# NanoRS485-MySens-v024.net
KiCad netlist of a schematic drawn in EAGLE
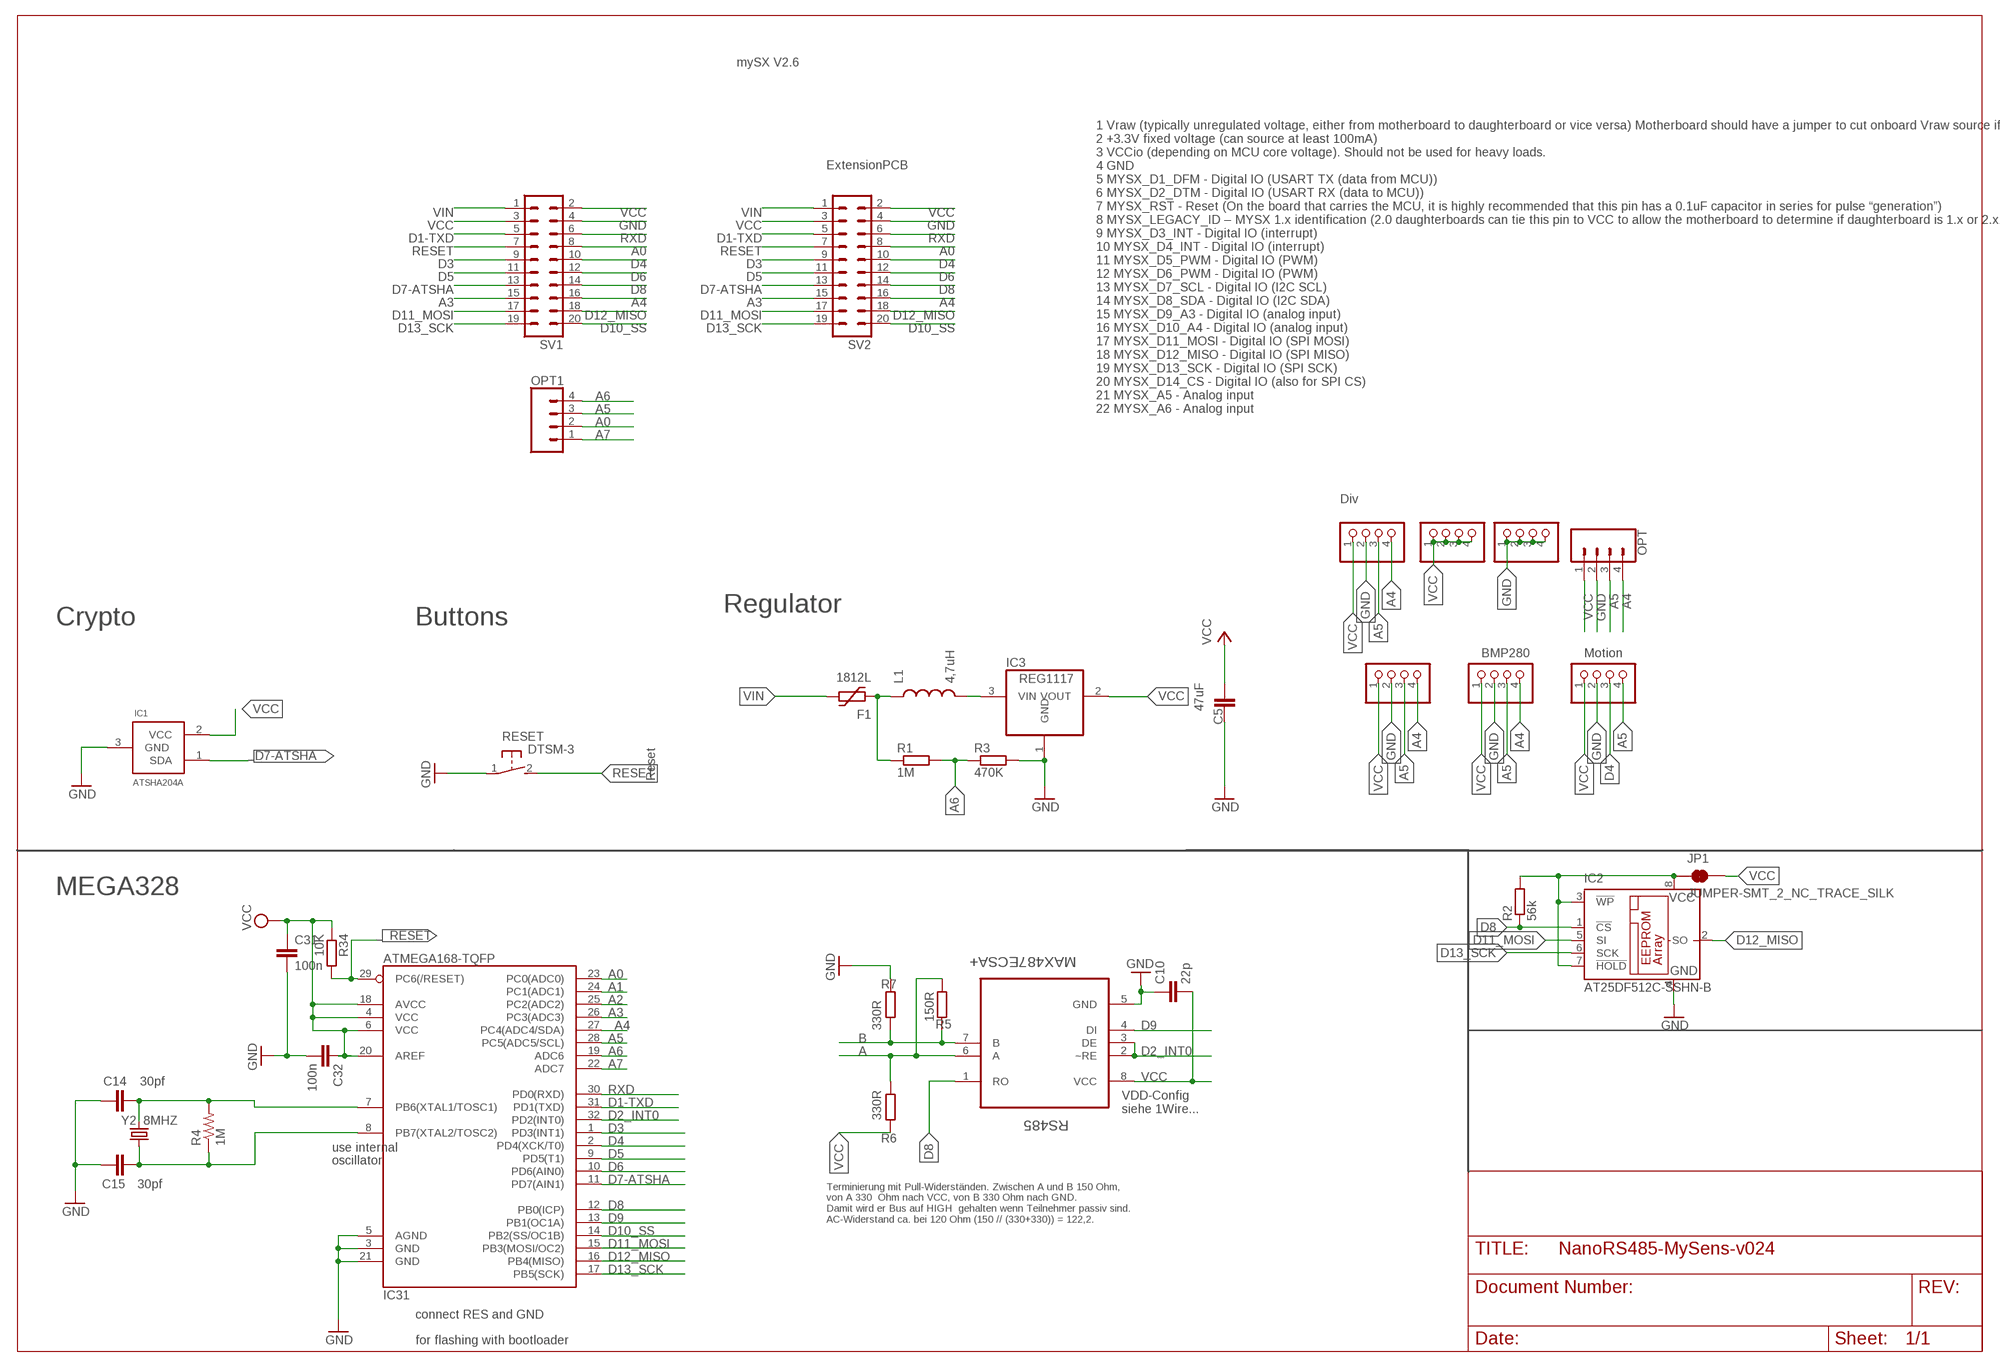
[diagram p0: schematic, sheet 1, part 1 of 2]
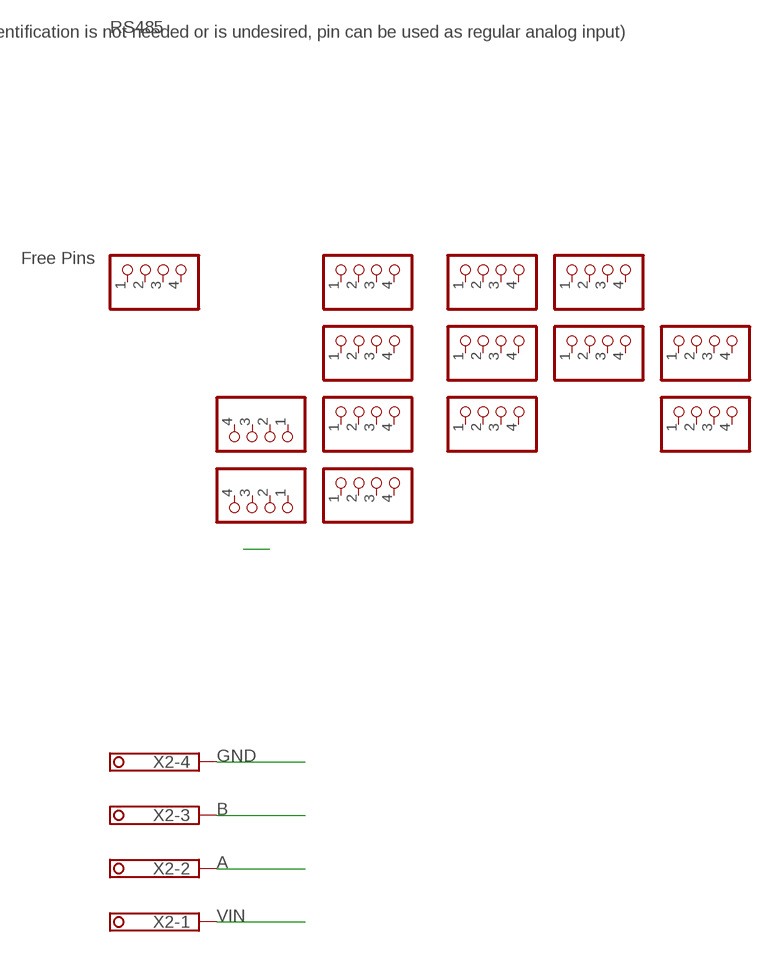
[diagram p1: schematic, sheet 1, part 2 of 2]

(export (version "E")
  (design (tool "Eeschema 10.0.6"))
  (components
    (comp (ref "BH1750")
      (value "PINHD-1X04_2.54-S")
      (footprint "eagle-import:1X04-S")
      (libsource (lib "eagle-import") (part "PINHD-1X04_2.54-S"))
    )
    (comp (ref "C5")
      (value "47uF")
      (footprint "eagle-import:C1210")
      (libsource (lib "eagle-import") (part "C-EUC1210"))
    )
    (comp (ref "C10")
      (value "22p")
      (footprint "eagle-import:C0805")
      (libsource (lib "eagle-import") (part "C-EUC0805"))
    )
    (comp (ref "C14")
      (value "30pf")
      (footprint "eagle-import:0805")
      (libsource (lib "eagle-import") (part "CAP0805"))
    )
    (comp (ref "C15")
      (value "30pf")
      (footprint "eagle-import:0805")
      (libsource (lib "eagle-import") (part "CAP0805"))
    )
    (comp (ref "C31")
      (value "100n")
      (footprint "eagle-import:C0805")
      (libsource (lib "eagle-import") (part "C-EUC0805"))
    )
    (comp (ref "C32")
      (value "100n")
      (footprint "eagle-import:C0805")
      (libsource (lib "eagle-import") (part "C-EUC0805"))
    )
    (comp (ref "F1")
      (value "1812L")
      (footprint "eagle-import:1812L")
      (libsource (lib "eagle-import") (part "1812L"))
    )
    (comp (ref "I2C-1")
      (value "PINHD-1X04_2.54-S")
      (footprint "eagle-import:1X04-S")
      (libsource (lib "eagle-import") (part "PINHD-1X04_2.54-S"))
    )
    (comp (ref "I2C-2")
      (value "PINHD-1X04_2.54-S")
      (footprint "eagle-import:1X04-S")
      (libsource (lib "eagle-import") (part "PINHD-1X04_2.54-S"))
    )
    (comp (ref "IC1")
      (value "ATSHA204A")
      (footprint "eagle-import:SOT23")
      (libsource (lib "eagle-import") (part "ATSHA204A"))
    )
    (comp (ref "IC2")
      (value "AT25DF512C-SSHN-B")
      (footprint "eagle-import:SO-08")
      (fields (field (name "MF") "MICROCHIP") (field (name "MPN") "25AA080/SN"))
      (libsource (lib "eagle-import") (part "25SNAA080"))
    )
    (comp (ref "IC3")
      (value "REG1117")
      (footprint "eagle-import:SOT223")
      (libsource (lib "eagle-import") (part "REG1117"))
    )
    (comp (ref "IC31")
      (value "ATMEGA168-TQFP")
      (footprint "eagle-import:TQFP32-08")
      (libsource (lib "eagle-import") (part "ATMEGA168-TQFP"))
    )
    (comp (ref "JP1")
      (value "JUMPER-SMT_2_NC_TRACE_SILK")
      (footprint "eagle-import:SMT-JUMPER_2_NC_TRACE_SILK")
      (libsource (lib "eagle-import") (part "JUMPER-SMT_2_NC_TRACE_SILK"))
    )
    (comp (ref "JP2")
      (value "PINHD-1X04_2.54-S")
      (footprint "eagle-import:1X04-S")
      (libsource (lib "eagle-import") (part "PINHD-1X04_2.54-S"))
    )
    (comp (ref "JP3")
      (value "PINHD-1X04_2.54-S")
      (footprint "eagle-import:1X04-S")
      (libsource (lib "eagle-import") (part "PINHD-1X04_2.54-S"))
    )
    (comp (ref "JP5")
      (value "PINHD-1X04_2.54-S")
      (footprint "eagle-import:1X04-S")
      (libsource (lib "eagle-import") (part "PINHD-1X04_2.54-S"))
    )
    (comp (ref "JP6")
      (value "PINHD-1X04_2.54-S")
      (footprint "eagle-import:1X04-S")
      (libsource (lib "eagle-import") (part "PINHD-1X04_2.54-S"))
    )
    (comp (ref "JP7")
      (value "PINHD-1X04_2.54-S")
      (footprint "eagle-import:1X04-S")
      (libsource (lib "eagle-import") (part "PINHD-1X04_2.54-S"))
    )
    (comp (ref "JP8")
      (value "PINHD-1X04_2.54-S")
      (footprint "eagle-import:1X04-S")
      (libsource (lib "eagle-import") (part "PINHD-1X04_2.54-S"))
    )
    (comp (ref "JP10")
      (value "PINHD-1X04_2.54-S")
      (footprint "eagle-import:1X04-S")
      (libsource (lib "eagle-import") (part "PINHD-1X04_2.54-S"))
    )
    (comp (ref "JP13")
      (value "PINHD-1X04_2.54-S")
      (footprint "eagle-import:1X04-S")
      (libsource (lib "eagle-import") (part "PINHD-1X04_2.54-S"))
    )
    (comp (ref "JP14")
      (value "PINHD-1X04_2.54-S")
      (footprint "eagle-import:1X04-S")
      (libsource (lib "eagle-import") (part "PINHD-1X04_2.54-S"))
    )
    (comp (ref "JP15")
      (value "PINHD-1X04_2.54-S")
      (footprint "eagle-import:1X04-S")
      (libsource (lib "eagle-import") (part "PINHD-1X04_2.54-S"))
    )
    (comp (ref "JP16")
      (value "PINHD-1X04_2.54-S")
      (footprint "eagle-import:1X04-S")
      (libsource (lib "eagle-import") (part "PINHD-1X04_2.54-S"))
    )
    (comp (ref "JP18")
      (value "PINHD-1X04_2.54-S")
      (footprint "eagle-import:1X04-S")
      (libsource (lib "eagle-import") (part "PINHD-1X04_2.54-S"))
    )
    (comp (ref "JP19")
      (value "PINHD-1X04_2.54-S")
      (footprint "eagle-import:1X04-S")
      (libsource (lib "eagle-import") (part "PINHD-1X04_2.54-S"))
    )
    (comp (ref "JP20")
      (value "PINHD-1X04_2.54-S")
      (footprint "eagle-import:1X04-S")
      (libsource (lib "eagle-import") (part "PINHD-1X04_2.54-S"))
    )
    (comp (ref "JP21")
      (value "PINHD-1X04_2.54-S")
      (footprint "eagle-import:1X04-S")
      (libsource (lib "eagle-import") (part "PINHD-1X04_2.54-S"))
    )
    (comp (ref "JP23")
      (value "PINHD-1X04_2.54-S")
      (footprint "eagle-import:1X04-S")
      (libsource (lib "eagle-import") (part "PINHD-1X04_2.54-S"))
    )
    (comp (ref "L1")
      (value "4,7uH")
      (footprint "eagle-import:0805")
      (libsource (lib "eagle-import") (part "INDUCTOR0805"))
    )
    (comp (ref "MOTION")
      (value "PINHD-1X04_2.54-S")
      (footprint "eagle-import:1X04-S")
      (libsource (lib "eagle-import") (part "PINHD-1X04_2.54-S"))
    )
    (comp (ref "OPT")
      (value "CONN_04")
      (footprint "eagle-import:1X04")
      (libsource (lib "eagle-import") (part "CONN_04"))
    )
    (comp (ref "OPT1")
      (value "CONN_04")
      (footprint "eagle-import:1X04")
      (libsource (lib "eagle-import") (part "CONN_04"))
    )
    (comp (ref "R1")
      (value "1M")
      (footprint "eagle-import:R0805")
      (libsource (lib "eagle-import") (part "R-EU_R0805"))
    )
    (comp (ref "R2")
      (value "56k")
      (footprint "eagle-import:M0805")
      (libsource (lib "eagle-import") (part "resistor_R-EU_M0805"))
    )
    (comp (ref "R3")
      (value "470K")
      (footprint "eagle-import:R0805")
      (libsource (lib "eagle-import") (part "R-EU_R0805"))
    )
    (comp (ref "R4")
      (value "1M")
      (footprint "eagle-import:0805")
      (libsource (lib "eagle-import") (part "RESISTOR0805-RES"))
    )
    (comp (ref "R5")
      (value "150R")
      (footprint "eagle-import:R0805")
      (libsource (lib "eagle-import") (part "R-EU_R0805"))
    )
    (comp (ref "R6")
      (value "330R")
      (footprint "eagle-import:R0805")
      (libsource (lib "eagle-import") (part "R-EU_R0805"))
    )
    (comp (ref "R7")
      (value "330R")
      (footprint "eagle-import:R0805")
      (libsource (lib "eagle-import") (part "R-EU_R0805"))
    )
    (comp (ref "R34")
      (value "10K")
      (footprint "eagle-import:R0805")
      (libsource (lib "eagle-import") (part "R-EU_R0805"))
    )
    (comp (ref "RESET")
      (value "DTSM-3")
      (footprint "eagle-import:DTSM-3")
      (libsource (lib "eagle-import") (part "DTSM-3"))
    )
    (comp (ref "RS485")
      (value "MAX487ECSA+")
      (footprint "eagle-import:SOIC127P600X175-8N")
      (libsource (lib "eagle-import") (part "MAX487ECSA+"))
    )
    (comp (ref "SV1")
      (value "MA10-2")
      (footprint "eagle-import:MA10-2")
      (libsource (lib "eagle-import") (part "MA10-2"))
    )
    (comp (ref "SV2")
      (value "MA10-2")
      (footprint "eagle-import:MA10-2")
      (libsource (lib "eagle-import") (part "MA10-2"))
    )
    (comp (ref "X2")
      (value "1751264")
      (footprint "eagle-import:1751264")
      (libsource (lib "eagle-import") (part "1751264"))
    )
    (comp (ref "Y2")
      (value "8MHZ")
      (footprint "eagle-import:CRYSTAL-TXC-7A")
      (libsource (lib "eagle-import") (part "CRYSTALTXC-7A"))
    )
  )
  (nets
    (net (code "1") (name "/A") (class "Default")
      (node (ref "R5") (pin "1") (pinfunction "1_1") (pintype "passive"))
      (node (ref "R6") (pin "2") (pinfunction "2_2") (pintype "passive"))
      (node (ref "RS485") (pin "6") (pinfunction "A_6") (pintype "bidirectional"))
      (node (ref "X2") (pin "2") (pinfunction "K_2") (pintype "passive"))
    )
    (net (code "2") (name "/A0") (class "Default")
      (node (ref "IC31") (pin "23") (pinfunction "PC0(ADC0)_23") (pintype "bidirectional"))
      (node (ref "OPT1") (pin "2") (pinfunction "2_2") (pintype "passive"))
      (node (ref "SV1") (pin "8") (pinfunction "8_8") (pintype "passive"))
      (node (ref "SV2") (pin "8") (pinfunction "8_8") (pintype "passive"))
    )
    (net (code "3") (name "/A1") (class "Default")
      (node (ref "IC31") (pin "24") (pinfunction "PC1(ADC1)_24") (pintype "bidirectional"))
    )
    (net (code "4") (name "/A2") (class "Default")
      (node (ref "IC31") (pin "25") (pinfunction "PC2(ADC2)_25") (pintype "bidirectional"))
    )
    (net (code "5") (name "/A3") (class "Default")
      (node (ref "IC31") (pin "26") (pinfunction "PC3(ADC3)_26") (pintype "bidirectional"))
      (node (ref "SV1") (pin "15") (pinfunction "15_15") (pintype "passive"))
      (node (ref "SV2") (pin "15") (pinfunction "15_15") (pintype "passive"))
    )
    (net (code "6") (name "/A7") (class "Default")
      (node (ref "IC31") (pin "22") (pinfunction "ADC7_22") (pintype "bidirectional"))
      (node (ref "OPT1") (pin "1") (pinfunction "1_1") (pintype "passive"))
    )
    (net (code "7") (name "/B") (class "Default")
      (node (ref "R5") (pin "2") (pinfunction "2_2") (pintype "passive"))
      (node (ref "R7") (pin "1") (pinfunction "1_1") (pintype "passive"))
      (node (ref "RS485") (pin "7") (pinfunction "B_7") (pintype "bidirectional"))
      (node (ref "X2") (pin "3") (pinfunction "K_3") (pintype "passive"))
    )
    (net (code "8") (name "/D1-TXD") (class "Default")
      (node (ref "IC31") (pin "31") (pinfunction "PD1(TXD)_31") (pintype "bidirectional"))
      (node (ref "SV1") (pin "5") (pinfunction "5_5") (pintype "passive"))
      (node (ref "SV2") (pin "5") (pinfunction "5_5") (pintype "passive"))
    )
    (net (code "9") (name "/D2_INT0") (class "Default")
      (node (ref "IC31") (pin "32") (pinfunction "PD2(INT0)_32") (pintype "bidirectional"))
      (node (ref "RS485") (pin "2") (pinfunction "~{RE}_2") (pintype "input"))
      (node (ref "RS485") (pin "3") (pinfunction "DE_3") (pintype "input"))
    )
    (net (code "10") (name "/D3") (class "Default")
      (node (ref "IC31") (pin "1") (pinfunction "PD3(INT1)_1") (pintype "bidirectional"))
      (node (ref "SV1") (pin "9") (pinfunction "9_9") (pintype "passive"))
      (node (ref "SV2") (pin "9") (pinfunction "9_9") (pintype "passive"))
    )
    (net (code "11") (name "/D5") (class "Default")
      (node (ref "IC31") (pin "9") (pinfunction "PD5(T1)_9") (pintype "bidirectional"))
      (node (ref "SV1") (pin "11") (pinfunction "11_11") (pintype "passive"))
      (node (ref "SV2") (pin "11") (pinfunction "11_11") (pintype "passive"))
    )
    (net (code "12") (name "/D6") (class "Default")
      (node (ref "IC31") (pin "10") (pinfunction "PD6(AIN0)_10") (pintype "bidirectional"))
      (node (ref "SV1") (pin "12") (pinfunction "12_12") (pintype "passive"))
      (node (ref "SV2") (pin "12") (pinfunction "12_12") (pintype "passive"))
    )
    (net (code "13") (name "/D7-ATSHA") (class "Default")
      (node (ref "IC1") (pin "1") (pinfunction "SDA_1") (pintype "bidirectional"))
      (node (ref "IC31") (pin "11") (pinfunction "PD7(AIN1)_11") (pintype "bidirectional"))
      (node (ref "SV1") (pin "13") (pinfunction "13_13") (pintype "passive"))
      (node (ref "SV2") (pin "13") (pinfunction "13_13") (pintype "passive"))
    )
    (net (code "14") (name "/D9") (class "Default")
      (node (ref "IC31") (pin "13") (pinfunction "PB1(OC1A)_13") (pintype "bidirectional"))
      (node (ref "RS485") (pin "4") (pinfunction "DI_4") (pintype "input"))
    )
    (net (code "15") (name "/D10_SS") (class "Default")
      (node (ref "IC31") (pin "14") (pinfunction "PB2(SS/OC1B)_14") (pintype "bidirectional"))
      (node (ref "SV1") (pin "20") (pinfunction "20_20") (pintype "passive"))
      (node (ref "SV2") (pin "20") (pinfunction "20_20") (pintype "passive"))
    )
    (net (code "16") (name "/RXD") (class "Default")
      (node (ref "IC31") (pin "30") (pinfunction "PD0(RXD)_30") (pintype "bidirectional"))
      (node (ref "SV1") (pin "6") (pinfunction "6_6") (pintype "passive"))
      (node (ref "SV2") (pin "6") (pinfunction "6_6") (pintype "passive"))
    )
    (net (code "17") (name "A4") (class "Default")
      (node (ref "BH1750") (pin "4") (pinfunction "4_4") (pintype "passive"))
      (node (ref "I2C-1") (pin "4") (pinfunction "4_4") (pintype "passive"))
      (node (ref "I2C-2") (pin "4") (pinfunction "4_4") (pintype "passive"))
      (node (ref "IC31") (pin "27") (pinfunction "PC4(ADC4/SDA)_27") (pintype "bidirectional"))
      (node (ref "OPT") (pin "4") (pinfunction "4_4") (pintype "passive"))
      (node (ref "SV1") (pin "16") (pinfunction "16_16") (pintype "passive"))
      (node (ref "SV2") (pin "16") (pinfunction "16_16") (pintype "passive"))
    )
    (net (code "18") (name "A5") (class "Default")
      (node (ref "BH1750") (pin "3") (pinfunction "3_3") (pintype "passive"))
      (node (ref "I2C-1") (pin "3") (pinfunction "3_3") (pintype "passive"))
      (node (ref "I2C-2") (pin "3") (pinfunction "3_3") (pintype "passive"))
      (node (ref "IC31") (pin "28") (pinfunction "PC5(ADC5/SCL)_28") (pintype "bidirectional"))
      (node (ref "MOTION") (pin "4") (pinfunction "4_4") (pintype "passive"))
      (node (ref "OPT") (pin "3") (pinfunction "3_3") (pintype "passive"))
      (node (ref "OPT1") (pin "3") (pinfunction "3_3") (pintype "passive"))
    )
    (net (code "19") (name "A6") (class "Default")
      (node (ref "IC31") (pin "19") (pinfunction "ADC6_19") (pintype "bidirectional"))
      (node (ref "OPT1") (pin "4") (pinfunction "4_4") (pintype "passive"))
      (node (ref "R1") (pin "2") (pinfunction "2_2") (pintype "passive"))
      (node (ref "R3") (pin "1") (pinfunction "1_1") (pintype "passive"))
    )
    (net (code "20") (name "D4") (class "Default")
      (node (ref "IC31") (pin "2") (pinfunction "PD4(XCK/T0)_2") (pintype "bidirectional"))
      (node (ref "MOTION") (pin "3") (pinfunction "3_3") (pintype "passive"))
      (node (ref "SV1") (pin "10") (pinfunction "10_10") (pintype "passive"))
      (node (ref "SV2") (pin "10") (pinfunction "10_10") (pintype "passive"))
    )
    (net (code "21") (name "D8") (class "Default")
      (node (ref "IC2") (pin "1") (pinfunction "~{CS}_1") (pintype "input"))
      (node (ref "IC31") (pin "12") (pinfunction "PB0(ICP)_12") (pintype "bidirectional"))
      (node (ref "R2") (pin "1") (pinfunction "1_1") (pintype "passive"))
      (node (ref "RS485") (pin "1") (pinfunction "RO_1") (pintype "output"))
      (node (ref "SV1") (pin "14") (pinfunction "14_14") (pintype "passive"))
      (node (ref "SV2") (pin "14") (pinfunction "14_14") (pintype "passive"))
    )
    (net (code "22") (name "D11_MOSI") (class "Default")
      (node (ref "IC2") (pin "5") (pinfunction "SI_5") (pintype "input"))
      (node (ref "IC31") (pin "15") (pinfunction "PB3(MOSI/OC2)_15") (pintype "bidirectional"))
      (node (ref "SV1") (pin "17") (pinfunction "17_17") (pintype "passive"))
      (node (ref "SV2") (pin "17") (pinfunction "17_17") (pintype "passive"))
    )
    (net (code "23") (name "D12_MISO") (class "Default")
      (node (ref "IC2") (pin "2") (pinfunction "SO_2") (pintype "bidirectional"))
      (node (ref "IC31") (pin "16") (pinfunction "PB4(MISO)_16") (pintype "bidirectional"))
      (node (ref "SV1") (pin "18") (pinfunction "18_18") (pintype "passive"))
      (node (ref "SV2") (pin "18") (pinfunction "18_18") (pintype "passive"))
    )
    (net (code "24") (name "D13_SCK") (class "Default")
      (node (ref "IC2") (pin "6") (pinfunction "SCK_6") (pintype "input"))
      (node (ref "IC31") (pin "17") (pinfunction "PB5(SCK)_17") (pintype "bidirectional"))
      (node (ref "SV1") (pin "19") (pinfunction "19_19") (pintype "passive"))
      (node (ref "SV2") (pin "19") (pinfunction "19_19") (pintype "passive"))
    )
    (net (code "25") (name "GND") (class "Default")
      (node (ref "BH1750") (pin "2") (pinfunction "2_2") (pintype "passive"))
      (node (ref "C10") (pin "1") (pinfunction "1_1") (pintype "passive"))
      (node (ref "C14") (pin "1") (pinfunction "1_1") (pintype "passive"))
      (node (ref "C15") (pin "1") (pinfunction "1_1") (pintype "passive"))
      (node (ref "C31") (pin "2") (pinfunction "2_2") (pintype "passive"))
      (node (ref "C32") (pin "2") (pinfunction "2_2") (pintype "passive"))
      (node (ref "C5") (pin "1") (pinfunction "1_1") (pintype "passive"))
      (node (ref "I2C-1") (pin "2") (pinfunction "2_2") (pintype "passive"))
      (node (ref "I2C-2") (pin "2") (pinfunction "2_2") (pintype "passive"))
      (node (ref "IC1") (pin "3") (pinfunction "GND_3") (pintype "bidirectional"))
      (node (ref "IC2") (pin "4") (pinfunction "GND_4") (pintype "power_in"))
      (node (ref "IC3") (pin "1") (pinfunction "GND_1") (pintype "power_in"))
      (node (ref "IC31") (pin "21") (pinfunction "GND_21") (pintype "bidirectional"))
      (node (ref "IC31") (pin "3") (pinfunction "GND_3") (pintype "bidirectional"))
      (node (ref "IC31") (pin "5") (pinfunction "AGND_5") (pintype "bidirectional"))
      (node (ref "JP2") (pin "1") (pinfunction "1_1") (pintype "passive"))
      (node (ref "JP2") (pin "2") (pinfunction "2_2") (pintype "passive"))
      (node (ref "JP2") (pin "3") (pinfunction "3_3") (pintype "passive"))
      (node (ref "JP2") (pin "4") (pinfunction "4_4") (pintype "passive"))
      (node (ref "MOTION") (pin "2") (pinfunction "2_2") (pintype "passive"))
      (node (ref "OPT") (pin "2") (pinfunction "2_2") (pintype "passive"))
      (node (ref "R3") (pin "2") (pinfunction "2_2") (pintype "passive"))
      (node (ref "R7") (pin "2") (pinfunction "2_2") (pintype "passive"))
      (node (ref "RESET") (pin "1") (pinfunction "1_1") (pintype "passive"))
      (node (ref "RS485") (pin "5") (pinfunction "GND_5") (pintype "passive"))
      (node (ref "SV1") (pin "4") (pinfunction "4_4") (pintype "passive"))
      (node (ref "SV2") (pin "4") (pinfunction "4_4") (pintype "passive"))
      (node (ref "X2") (pin "4") (pinfunction "K_4") (pintype "passive"))
    )
    (net (code "26") (name "Net-(F1-1)") (class "Default")
      (node (ref "F1") (pin "P$1") (pinfunction "1_P$1") (pintype "passive"))
      (node (ref "L1") (pin "1") (pinfunction "1_1") (pintype "passive"))
      (node (ref "R1") (pin "1") (pinfunction "1_1") (pintype "passive"))
    )
    (net (code "27") (name "Net-(IC2-VCC)") (class "Default")
      (node (ref "IC2") (pin "3") (pinfunction "~{WP}_3") (pintype "input"))
      (node (ref "IC2") (pin "7") (pinfunction "~{HOLD}_7") (pintype "input"))
      (node (ref "IC2") (pin "8") (pinfunction "VCC_8") (pintype "power_in"))
      (node (ref "JP1") (pin "1") (pinfunction "1_1") (pintype "passive"))
      (node (ref "R2") (pin "2") (pinfunction "2_2") (pintype "passive"))
    )
    (net (code "28") (name "Net-(IC3-VIN)") (class "Default")
      (node (ref "IC3") (pin "3") (pinfunction "VIN_3") (pintype "input"))
      (node (ref "L1") (pin "2") (pinfunction "2_2") (pintype "passive"))
    )
    (net (code "29") (name "Net-(IC31-PB6(XTAL1{slash}TOSC1))") (class "Default")
      (node (ref "C14") (pin "2") (pinfunction "2_2") (pintype "passive"))
      (node (ref "IC31") (pin "7") (pinfunction "PB6(XTAL1/TOSC1)_7") (pintype "bidirectional"))
      (node (ref "R4") (pin "2") (pinfunction "2_2") (pintype "passive"))
      (node (ref "Y2") (pin "P$2") (pinfunction "2_P$2") (pintype "passive"))
    )
    (net (code "30") (name "Net-(IC31-PB7(XTAL2{slash}TOSC2))") (class "Default")
      (node (ref "C15") (pin "2") (pinfunction "2_2") (pintype "passive"))
      (node (ref "IC31") (pin "8") (pinfunction "PB7(XTAL2/TOSC2)_8") (pintype "bidirectional"))
      (node (ref "R4") (pin "1") (pinfunction "1_1") (pintype "passive"))
      (node (ref "Y2") (pin "P$1") (pinfunction "1_P$1") (pintype "passive"))
    )
    (net (code "31") (name "RESET") (class "Default")
      (node (ref "IC31") (pin "29") (pinfunction "PC6(/RESET)_29") (pintype "bidirectional"))
      (node (ref "R34") (pin "2") (pinfunction "2_2") (pintype "passive"))
      (node (ref "RESET") (pin "2") (pinfunction "2_2") (pintype "passive"))
      (node (ref "SV1") (pin "7") (pinfunction "7_7") (pintype "passive"))
      (node (ref "SV2") (pin "7") (pinfunction "7_7") (pintype "passive"))
    )
    (net (code "32") (name "VCC") (class "Default")
      (node (ref "BH1750") (pin "1") (pinfunction "1_1") (pintype "passive"))
      (node (ref "C10") (pin "2") (pinfunction "2_2") (pintype "passive"))
      (node (ref "C31") (pin "1") (pinfunction "1_1") (pintype "passive"))
      (node (ref "C32") (pin "1") (pinfunction "1_1") (pintype "passive"))
      (node (ref "C5") (pin "2") (pinfunction "2_2") (pintype "passive"))
      (node (ref "I2C-1") (pin "1") (pinfunction "1_1") (pintype "passive"))
      (node (ref "I2C-2") (pin "1") (pinfunction "1_1") (pintype "passive"))
      (node (ref "IC1") (pin "2") (pinfunction "VCC_2") (pintype "bidirectional"))
      (node (ref "IC3") (pin "2") (pinfunction "VOUT_2") (pintype "output"))
      (node (ref "IC31") (pin "18") (pinfunction "AVCC_18") (pintype "bidirectional"))
      (node (ref "IC31") (pin "20") (pinfunction "AREF_20") (pintype "bidirectional"))
      (node (ref "IC31") (pin "4") (pinfunction "VCC_4") (pintype "bidirectional"))
      (node (ref "IC31") (pin "6") (pinfunction "VCC_6") (pintype "bidirectional"))
      (node (ref "JP1") (pin "2") (pinfunction "2_2") (pintype "passive"))
      (node (ref "JP3") (pin "1") (pinfunction "1_1") (pintype "passive"))
      (node (ref "JP3") (pin "2") (pinfunction "2_2") (pintype "passive"))
      (node (ref "JP3") (pin "3") (pinfunction "3_3") (pintype "passive"))
      (node (ref "JP3") (pin "4") (pinfunction "4_4") (pintype "passive"))
      (node (ref "MOTION") (pin "1") (pinfunction "1_1") (pintype "passive"))
      (node (ref "OPT") (pin "1") (pinfunction "1_1") (pintype "passive"))
      (node (ref "R34") (pin "1") (pinfunction "1_1") (pintype "passive"))
      (node (ref "R6") (pin "1") (pinfunction "1_1") (pintype "passive"))
      (node (ref "RS485") (pin "8") (pinfunction "VCC_8") (pintype "power_in"))
      (node (ref "SV1") (pin "2") (pinfunction "2_2") (pintype "passive"))
      (node (ref "SV1") (pin "3") (pinfunction "3_3") (pintype "passive"))
      (node (ref "SV2") (pin "2") (pinfunction "2_2") (pintype "passive"))
      (node (ref "SV2") (pin "3") (pinfunction "3_3") (pintype "passive"))
    )
    (net (code "33") (name "VIN") (class "Default")
      (node (ref "F1") (pin "P$2") (pinfunction "2_P$2") (pintype "passive"))
      (node (ref "SV1") (pin "1") (pinfunction "1_1") (pintype "passive"))
      (node (ref "SV2") (pin "1") (pinfunction "1_1") (pintype "passive"))
      (node (ref "X2") (pin "1") (pinfunction "K_1") (pintype "passive"))
    )
    (net (code "34") (name "unconnected-(JP5-Pad1)") (class "Default")
      (node (ref "JP5") (pin "1") (pinfunction "1_1") (pintype "passive"))
    )
    (net (code "35") (name "unconnected-(JP5-Pad2)") (class "Default")
      (node (ref "JP5") (pin "2") (pinfunction "2_2") (pintype "passive"))
    )
    (net (code "36") (name "unconnected-(JP5-Pad3)") (class "Default")
      (node (ref "JP5") (pin "3") (pinfunction "3_3") (pintype "passive"))
    )
    (net (code "37") (name "unconnected-(JP5-Pad4)") (class "Default")
      (node (ref "JP5") (pin "4") (pinfunction "4_4") (pintype "passive"))
    )
    (net (code "38") (name "unconnected-(JP6-Pad1)") (class "Default")
      (node (ref "JP6") (pin "1") (pinfunction "1_1") (pintype "passive"))
    )
    (net (code "39") (name "unconnected-(JP6-Pad2)") (class "Default")
      (node (ref "JP6") (pin "2") (pinfunction "2_2") (pintype "passive"))
    )
    (net (code "40") (name "unconnected-(JP6-Pad3)") (class "Default")
      (node (ref "JP6") (pin "3") (pinfunction "3_3") (pintype "passive"))
    )
    (net (code "41") (name "unconnected-(JP6-Pad4)") (class "Default")
      (node (ref "JP6") (pin "4") (pinfunction "4_4") (pintype "passive"))
    )
    (net (code "42") (name "unconnected-(JP7-Pad1)") (class "Default")
      (node (ref "JP7") (pin "1") (pinfunction "1_1") (pintype "passive"))
    )
    (net (code "43") (name "unconnected-(JP7-Pad2)") (class "Default")
      (node (ref "JP7") (pin "2") (pinfunction "2_2") (pintype "passive"))
    )
    (net (code "44") (name "unconnected-(JP7-Pad3)") (class "Default")
      (node (ref "JP7") (pin "3") (pinfunction "3_3") (pintype "passive"))
    )
    (net (code "45") (name "unconnected-(JP7-Pad4)") (class "Default")
      (node (ref "JP7") (pin "4") (pinfunction "4_4") (pintype "passive"))
    )
    (net (code "46") (name "unconnected-(JP8-Pad1)") (class "Default")
      (node (ref "JP8") (pin "1") (pinfunction "1_1") (pintype "passive"))
    )
    (net (code "47") (name "unconnected-(JP8-Pad2)") (class "Default")
      (node (ref "JP8") (pin "2") (pinfunction "2_2") (pintype "passive"))
    )
    (net (code "48") (name "unconnected-(JP8-Pad3)") (class "Default")
      (node (ref "JP8") (pin "3") (pinfunction "3_3") (pintype "passive"))
    )
    (net (code "49") (name "unconnected-(JP8-Pad4)") (class "Default")
      (node (ref "JP8") (pin "4") (pinfunction "4_4") (pintype "passive"))
    )
    (net (code "50") (name "unconnected-(JP10-Pad1)") (class "Default")
      (node (ref "JP10") (pin "1") (pinfunction "1_1") (pintype "passive"))
    )
    (net (code "51") (name "unconnected-(JP10-Pad2)") (class "Default")
      (node (ref "JP10") (pin "2") (pinfunction "2_2") (pintype "passive"))
    )
    (net (code "52") (name "unconnected-(JP10-Pad3)") (class "Default")
      (node (ref "JP10") (pin "3") (pinfunction "3_3") (pintype "passive"))
    )
    (net (code "53") (name "unconnected-(JP10-Pad4)") (class "Default")
      (node (ref "JP10") (pin "4") (pinfunction "4_4") (pintype "passive"))
    )
    (net (code "54") (name "unconnected-(JP13-Pad1)") (class "Default")
      (node (ref "JP13") (pin "1") (pinfunction "1_1") (pintype "passive"))
    )
    (net (code "55") (name "unconnected-(JP13-Pad2)") (class "Default")
      (node (ref "JP13") (pin "2") (pinfunction "2_2") (pintype "passive"))
    )
    (net (code "56") (name "unconnected-(JP13-Pad3)") (class "Default")
      (node (ref "JP13") (pin "3") (pinfunction "3_3") (pintype "passive"))
    )
    (net (code "57") (name "unconnected-(JP13-Pad4)") (class "Default")
      (node (ref "JP13") (pin "4") (pinfunction "4_4") (pintype "passive"))
    )
    (net (code "58") (name "unconnected-(JP14-Pad1)") (class "Default")
      (node (ref "JP14") (pin "1") (pinfunction "1_1") (pintype "passive"))
    )
    (net (code "59") (name "unconnected-(JP14-Pad2)") (class "Default")
      (node (ref "JP14") (pin "2") (pinfunction "2_2") (pintype "passive"))
    )
    (net (code "60") (name "unconnected-(JP14-Pad3)") (class "Default")
      (node (ref "JP14") (pin "3") (pinfunction "3_3") (pintype "passive"))
    )
    (net (code "61") (name "unconnected-(JP14-Pad4)") (class "Default")
      (node (ref "JP14") (pin "4") (pinfunction "4_4") (pintype "passive"))
    )
    (net (code "62") (name "unconnected-(JP15-Pad1)") (class "Default")
      (node (ref "JP15") (pin "1") (pinfunction "1_1") (pintype "passive"))
    )
    (net (code "63") (name "unconnected-(JP15-Pad2)") (class "Default")
      (node (ref "JP15") (pin "2") (pinfunction "2_2") (pintype "passive"))
    )
    (net (code "64") (name "unconnected-(JP15-Pad3)") (class "Default")
      (node (ref "JP15") (pin "3") (pinfunction "3_3") (pintype "passive"))
    )
    (net (code "65") (name "unconnected-(JP15-Pad4)") (class "Default")
      (node (ref "JP15") (pin "4") (pinfunction "4_4") (pintype "passive"))
    )
    (net (code "66") (name "unconnected-(JP16-Pad1)") (class "Default")
      (node (ref "JP16") (pin "1") (pinfunction "1_1") (pintype "passive"))
    )
    (net (code "67") (name "unconnected-(JP16-Pad2)") (class "Default")
      (node (ref "JP16") (pin "2") (pinfunction "2_2") (pintype "passive"))
    )
    (net (code "68") (name "unconnected-(JP16-Pad3)") (class "Default")
      (node (ref "JP16") (pin "3") (pinfunction "3_3") (pintype "passive"))
    )
    (net (code "69") (name "unconnected-(JP16-Pad4)") (class "Default")
      (node (ref "JP16") (pin "4") (pinfunction "4_4") (pintype "passive"))
    )
    (net (code "70") (name "unconnected-(JP18-Pad1)") (class "Default")
      (node (ref "JP18") (pin "1") (pinfunction "1_1") (pintype "passive"))
    )
    (net (code "71") (name "unconnected-(JP18-Pad2)") (class "Default")
      (node (ref "JP18") (pin "2") (pinfunction "2_2") (pintype "passive"))
    )
    (net (code "72") (name "unconnected-(JP18-Pad3)") (class "Default")
      (node (ref "JP18") (pin "3") (pinfunction "3_3") (pintype "passive"))
    )
    (net (code "73") (name "unconnected-(JP18-Pad4)") (class "Default")
      (node (ref "JP18") (pin "4") (pinfunction "4_4") (pintype "passive"))
    )
    (net (code "74") (name "unconnected-(JP19-Pad1)") (class "Default")
      (node (ref "JP19") (pin "1") (pinfunction "1_1") (pintype "passive"))
    )
    (net (code "75") (name "unconnected-(JP19-Pad2)") (class "Default")
      (node (ref "JP19") (pin "2") (pinfunction "2_2") (pintype "passive"))
    )
    (net (code "76") (name "unconnected-(JP19-Pad3)") (class "Default")
      (node (ref "JP19") (pin "3") (pinfunction "3_3") (pintype "passive"))
    )
    (net (code "77") (name "unconnected-(JP19-Pad4)") (class "Default")
      (node (ref "JP19") (pin "4") (pinfunction "4_4") (pintype "passive"))
    )
    (net (code "78") (name "unconnected-(JP20-Pad1)") (class "Default")
      (node (ref "JP20") (pin "1") (pinfunction "1_1") (pintype "passive"))
    )
    (net (code "79") (name "unconnected-(JP20-Pad2)") (class "Default")
      (node (ref "JP20") (pin "2") (pinfunction "2_2") (pintype "passive"))
    )
    (net (code "80") (name "unconnected-(JP20-Pad3)") (class "Default")
      (node (ref "JP20") (pin "3") (pinfunction "3_3") (pintype "passive"))
    )
    (net (code "81") (name "unconnected-(JP20-Pad4)") (class "Default")
      (node (ref "JP20") (pin "4") (pinfunction "4_4") (pintype "passive"))
    )
    (net (code "82") (name "unconnected-(JP21-Pad1)") (class "Default")
      (node (ref "JP21") (pin "1") (pinfunction "1_1") (pintype "passive"))
    )
    (net (code "83") (name "unconnected-(JP21-Pad2)") (class "Default")
      (node (ref "JP21") (pin "2") (pinfunction "2_2") (pintype "passive"))
    )
    (net (code "84") (name "unconnected-(JP21-Pad3)") (class "Default")
      (node (ref "JP21") (pin "3") (pinfunction "3_3") (pintype "passive"))
    )
    (net (code "85") (name "unconnected-(JP21-Pad4)") (class "Default")
      (node (ref "JP21") (pin "4") (pinfunction "4_4") (pintype "passive"))
    )
    (net (code "86") (name "unconnected-(JP23-Pad1)") (class "Default")
      (node (ref "JP23") (pin "1") (pinfunction "1_1") (pintype "passive"))
    )
    (net (code "87") (name "unconnected-(JP23-Pad2)") (class "Default")
      (node (ref "JP23") (pin "2") (pinfunction "2_2") (pintype "passive"))
    )
    (net (code "88") (name "unconnected-(JP23-Pad3)") (class "Default")
      (node (ref "JP23") (pin "3") (pinfunction "3_3") (pintype "passive"))
    )
    (net (code "89") (name "unconnected-(JP23-Pad4)") (class "Default")
      (node (ref "JP23") (pin "4") (pinfunction "4_4") (pintype "passive"))
    )
  )
)
